# VNH7070AS_motor_driver.net
KiCad netlist of a schematic drawn in EAGLE
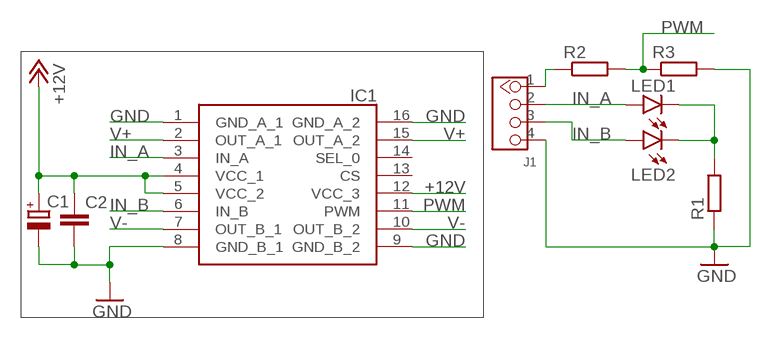
[diagram p0: schematic, sheet 1]

(export (version "E")
  (design (tool "Eeschema 10.0.6"))
  (components
    (comp (ref "C1")
      (value "CPOL-EUCT7343")
      (footprint "eagle-import:CT7343")
      (libsource (lib "eagle-import") (part "CPOL-EUCT7343"))
    )
    (comp (ref "C2")
      (value "C-EUC0805")
      (footprint "eagle-import:C0805")
      (libsource (lib "eagle-import") (part "C-EUC0805"))
    )
    (comp (ref "IC1")
      (value "VNH7070ASTR")
      (footprint "eagle-import:SOIC127P600X175-16N")
      (fields
        (field (name "MOUSER_PART_NUMBER") "511-VNH7070ASTR")
        (field (name "RS_PART_NUMBER") "1647017P")
      )
      (libsource (lib "eagle-import") (part "VNH7070ASTR"))
    )
    (comp (ref "J1")
      (value "TWIG_2.0")
      (footprint "eagle-import:2.0_1X4")
      (libsource (lib "eagle-import") (part "TWIG_2.0"))
    )
    (comp (ref "LED1")
      (value "LEDCHIPLED_1206")
      (footprint "eagle-import:CHIPLED_1206")
      (libsource (lib "eagle-import") (part "LEDCHIPLED_1206"))
    )
    (comp (ref "LED2")
      (value "LEDCHIPLED_1206")
      (footprint "eagle-import:CHIPLED_1206")
      (libsource (lib "eagle-import") (part "LEDCHIPLED_1206"))
    )
    (comp (ref "R1")
      (value "R-EU_R0805")
      (footprint "eagle-import:R0805")
      (libsource (lib "eagle-import") (part "R-EU_R0805"))
    )
    (comp (ref "R2")
      (value "R-EU_R0805")
      (footprint "eagle-import:R0805")
      (libsource (lib "eagle-import") (part "R-EU_R0805"))
    )
    (comp (ref "R3")
      (value "R-EU_R0805")
      (footprint "eagle-import:R0805")
      (libsource (lib "eagle-import") (part "R-EU_R0805"))
    )
  )
  (nets
    (net (code "1") (name "+12V") (class "Default")
      (node (ref "C1") (pin "+") (pinfunction "+_+") (pintype "passive"))
      (node (ref "C2") (pin "1") (pinfunction "1_1") (pintype "passive"))
      (node (ref "IC1") (pin "12") (pinfunction "VCC_3_12") (pintype "bidirectional"))
      (node (ref "IC1") (pin "4") (pinfunction "VCC_1_4") (pintype "bidirectional"))
      (node (ref "IC1") (pin "5") (pinfunction "VCC_2_5") (pintype "bidirectional"))
    )
    (net (code "2") (name "/IN_A") (class "Default")
      (node (ref "IC1") (pin "3") (pinfunction "IN_A_3") (pintype "bidirectional"))
      (node (ref "J1") (pin "2") (pinfunction "2_2") (pintype "bidirectional"))
      (node (ref "LED1") (pin "A") (pinfunction "A_A") (pintype "passive"))
    )
    (net (code "3") (name "/IN_B") (class "Default")
      (node (ref "IC1") (pin "6") (pinfunction "IN_B_6") (pintype "bidirectional"))
      (node (ref "J1") (pin "3") (pinfunction "3_3") (pintype "bidirectional"))
      (node (ref "LED2") (pin "A") (pinfunction "A_A") (pintype "passive"))
    )
    (net (code "4") (name "/PWM") (class "Default")
      (node (ref "IC1") (pin "11") (pinfunction "PWM_11") (pintype "bidirectional"))
      (node (ref "R2") (pin "2") (pinfunction "2_2") (pintype "passive"))
      (node (ref "R3") (pin "1") (pinfunction "1_1") (pintype "passive"))
    )
    (net (code "5") (name "/V+") (class "Default")
      (node (ref "IC1") (pin "15") (pinfunction "OUT_A_2_15") (pintype "bidirectional"))
      (node (ref "IC1") (pin "2") (pinfunction "OUT_A_1_2") (pintype "bidirectional"))
    )
    (net (code "6") (name "/V-") (class "Default")
      (node (ref "IC1") (pin "10") (pinfunction "OUT_B_2_10") (pintype "bidirectional"))
      (node (ref "IC1") (pin "7") (pinfunction "OUT_B_1_7") (pintype "bidirectional"))
    )
    (net (code "7") (name "GND") (class "Default")
      (node (ref "C1") (pin "-") (pinfunction "-_-") (pintype "passive"))
      (node (ref "C2") (pin "2") (pinfunction "2_2") (pintype "passive"))
      (node (ref "IC1") (pin "1") (pinfunction "GND_A_1_1") (pintype "bidirectional"))
      (node (ref "IC1") (pin "16") (pinfunction "GND_A_2_16") (pintype "bidirectional"))
      (node (ref "IC1") (pin "8") (pinfunction "GND_B_1_8") (pintype "bidirectional"))
      (node (ref "IC1") (pin "9") (pinfunction "GND_B_2_9") (pintype "bidirectional"))
      (node (ref "J1") (pin "4") (pinfunction "4_4") (pintype "bidirectional"))
      (node (ref "R1") (pin "1") (pinfunction "1_1") (pintype "passive"))
      (node (ref "R3") (pin "2") (pinfunction "2_2") (pintype "passive"))
    )
    (net (code "8") (name "Net-(J1-Pad1)") (class "Default")
      (node (ref "J1") (pin "1") (pinfunction "1_1") (pintype "bidirectional"))
      (node (ref "R2") (pin "1") (pinfunction "1_1") (pintype "passive"))
    )
    (net (code "9") (name "Net-(LED1-PadC)") (class "Default")
      (node (ref "LED1") (pin "C") (pinfunction "C_C") (pintype "passive"))
      (node (ref "LED2") (pin "C") (pinfunction "C_C") (pintype "passive"))
      (node (ref "R1") (pin "2") (pinfunction "2_2") (pintype "passive"))
    )
    (net (code "10") (name "unconnected-(IC1-CS-Pad13)") (class "Default")
      (node (ref "IC1") (pin "13") (pinfunction "CS_13") (pintype "bidirectional"))
    )
    (net (code "11") (name "unconnected-(IC1-SEL_0-Pad14)") (class "Default")
      (node (ref "IC1") (pin "14") (pinfunction "SEL_0_14") (pintype "bidirectional"))
    )
  )
)
